# PWDTimer_8Lane.net
KiCad netlist of a schematic drawn in EAGLE
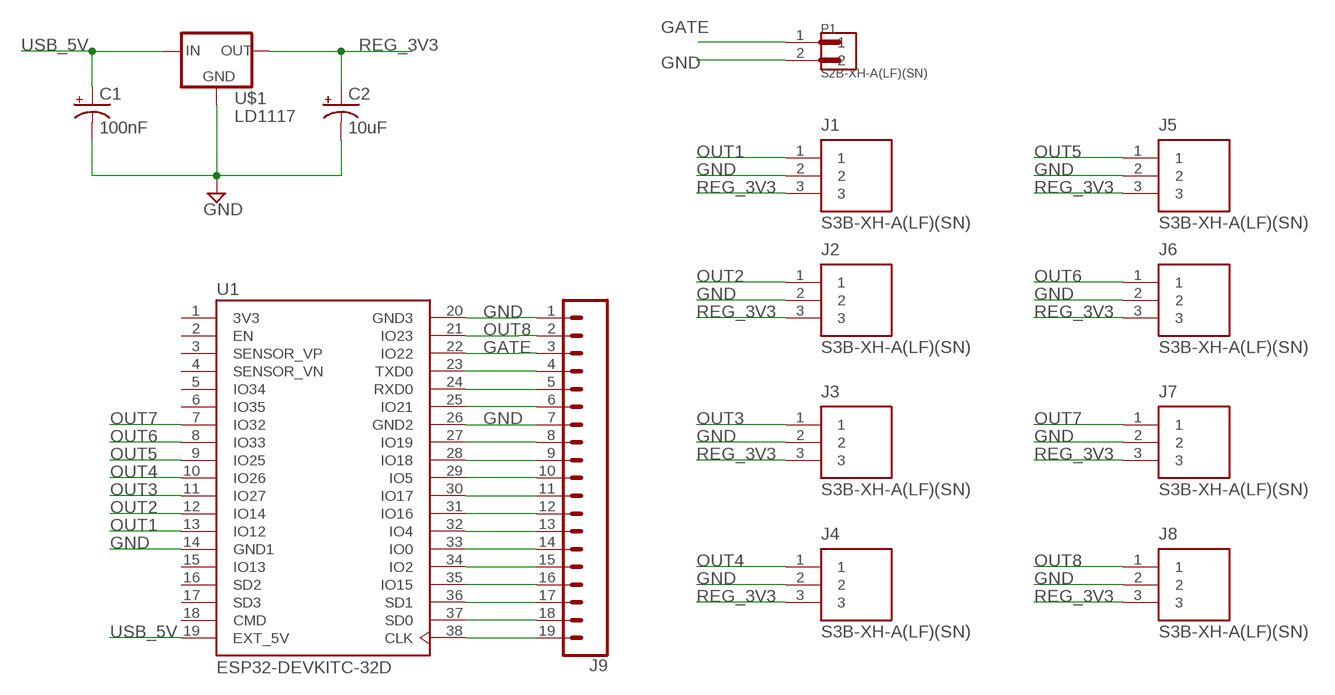
[diagram p0: schematic, sheet 1]

(export (version "E")
  (design (tool "Eeschema 10.0.6"))
  (components
    (comp (ref "C1")
      (value "100nF")
      (footprint "eagle-import:CPOL-RADIAL-2.5MM-5MM")
      (libsource (lib "eagle-import") (part "10UF-POLAR-RADIAL-2.5MM-25V-20%"))
    )
    (comp (ref "C2")
      (value "10uF")
      (footprint "eagle-import:CPOL-RADIAL-2.5MM-5MM")
      (libsource (lib "eagle-import") (part "10UF-POLAR-RADIAL-2.5MM-25V-20%"))
    )
    (comp (ref "J1")
      (value "S3B-XH-A(LF)(SN)")
      (footprint "eagle-import:JST_S3B-XH-A(LF)(SN)")
      (fields (field (name "MF") "JST Sales America Inc."))
      (libsource (lib "eagle-import") (part "S3B-XH-A(LF)(SN)"))
    )
    (comp (ref "J2")
      (value "S3B-XH-A(LF)(SN)")
      (footprint "eagle-import:JST_S3B-XH-A(LF)(SN)")
      (fields (field (name "MF") "JST Sales America Inc."))
      (libsource (lib "eagle-import") (part "S3B-XH-A(LF)(SN)"))
    )
    (comp (ref "J3")
      (value "S3B-XH-A(LF)(SN)")
      (footprint "eagle-import:JST_S3B-XH-A(LF)(SN)")
      (fields (field (name "MF") "JST Sales America Inc."))
      (libsource (lib "eagle-import") (part "S3B-XH-A(LF)(SN)"))
    )
    (comp (ref "J4")
      (value "S3B-XH-A(LF)(SN)")
      (footprint "eagle-import:JST_S3B-XH-A(LF)(SN)")
      (fields (field (name "MF") "JST Sales America Inc."))
      (libsource (lib "eagle-import") (part "S3B-XH-A(LF)(SN)"))
    )
    (comp (ref "J5")
      (value "S3B-XH-A(LF)(SN)")
      (footprint "eagle-import:JST_S3B-XH-A(LF)(SN)")
      (fields (field (name "MF") "JST Sales America Inc."))
      (libsource (lib "eagle-import") (part "S3B-XH-A(LF)(SN)"))
    )
    (comp (ref "J6")
      (value "S3B-XH-A(LF)(SN)")
      (footprint "eagle-import:JST_S3B-XH-A(LF)(SN)")
      (fields (field (name "MF") "JST Sales America Inc."))
      (libsource (lib "eagle-import") (part "S3B-XH-A(LF)(SN)"))
    )
    (comp (ref "J7")
      (value "S3B-XH-A(LF)(SN)")
      (footprint "eagle-import:JST_S3B-XH-A(LF)(SN)")
      (fields (field (name "MF") "JST Sales America Inc."))
      (libsource (lib "eagle-import") (part "S3B-XH-A(LF)(SN)"))
    )
    (comp (ref "J8")
      (value "S3B-XH-A(LF)(SN)")
      (footprint "eagle-import:JST_S3B-XH-A(LF)(SN)")
      (fields (field (name "MF") "JST Sales America Inc."))
      (libsource (lib "eagle-import") (part "S3B-XH-A(LF)(SN)"))
    )
    (comp (ref "J9")
      (value "CONN_191X19_NO_SILK")
      (footprint "eagle-import:1X19_NO_SILK")
      (libsource (lib "eagle-import") (part "CONN_191X19_NO_SILK"))
    )
    (comp (ref "P1")
      (value "S2B-XH-A(LF)(SN)")
      (footprint "eagle-import:JST_S2B-XH-A(LF)(SN)")
      (fields (field (name "MF") "JST Sales"))
      (libsource (lib "eagle-import") (part "S2B-XH-A(LF)(SN)"))
    )
    (comp (ref "U$1")
      (value "LD1117")
      (footprint "eagle-import:TO220")
      (fields (field (name "MF") "STMicroelectronics"))
      (libsource (lib "eagle-import") (part "LD1117"))
    )
    (comp (ref "U1")
      (value "ESP32-DEVKITC-32D")
      (footprint "eagle-import:MODULE_ESP32-DEVKITC-32D")
      (fields (field (name "MF") "Espressif Systems"))
      (libsource (lib "eagle-import") (part "ESP32-DEVKITC-32D"))
    )
  )
  (nets
    (net (code "1") (name "/3V3") (class "Default")
      (node (ref "U1") (pin "1") (pinfunction "3V3_1") (pintype "power_in"))
    )
    (net (code "2") (name "/GATE") (class "Default")
      (node (ref "J9") (pin "3") (pinfunction "3_3") (pintype "passive"))
      (node (ref "P1") (pin "1") (pinfunction "1_1") (pintype "passive"))
      (node (ref "U1") (pin "22") (pinfunction "IO22_22") (pintype "bidirectional"))
    )
    (net (code "3") (name "/OUT1") (class "Default")
      (node (ref "J1") (pin "1") (pinfunction "1_1") (pintype "passive"))
      (node (ref "U1") (pin "13") (pinfunction "IO12_13") (pintype "bidirectional"))
    )
    (net (code "4") (name "/OUT2") (class "Default")
      (node (ref "J2") (pin "1") (pinfunction "1_1") (pintype "passive"))
      (node (ref "U1") (pin "12") (pinfunction "IO14_12") (pintype "bidirectional"))
    )
    (net (code "5") (name "/OUT3") (class "Default")
      (node (ref "J3") (pin "1") (pinfunction "1_1") (pintype "passive"))
      (node (ref "U1") (pin "11") (pinfunction "IO27_11") (pintype "bidirectional"))
    )
    (net (code "6") (name "/OUT4") (class "Default")
      (node (ref "J4") (pin "1") (pinfunction "1_1") (pintype "passive"))
      (node (ref "U1") (pin "10") (pinfunction "IO26_10") (pintype "bidirectional"))
    )
    (net (code "7") (name "/OUT5") (class "Default")
      (node (ref "J5") (pin "1") (pinfunction "1_1") (pintype "passive"))
      (node (ref "U1") (pin "9") (pinfunction "IO25_9") (pintype "bidirectional"))
    )
    (net (code "8") (name "/OUT6") (class "Default")
      (node (ref "J6") (pin "1") (pinfunction "1_1") (pintype "passive"))
      (node (ref "U1") (pin "8") (pinfunction "IO33_8") (pintype "bidirectional"))
    )
    (net (code "9") (name "/OUT7") (class "Default")
      (node (ref "J7") (pin "1") (pinfunction "1_1") (pintype "passive"))
      (node (ref "U1") (pin "7") (pinfunction "IO32_7") (pintype "bidirectional"))
    )
    (net (code "10") (name "/OUT8") (class "Default")
      (node (ref "J8") (pin "1") (pinfunction "1_1") (pintype "passive"))
      (node (ref "J9") (pin "2") (pinfunction "2_2") (pintype "passive"))
      (node (ref "U1") (pin "21") (pinfunction "IO23_21") (pintype "bidirectional"))
    )
    (net (code "11") (name "/REG_3V3") (class "Default")
      (node (ref "C2") (pin "1") (pinfunction "+_1") (pintype "passive"))
      (node (ref "J1") (pin "3") (pinfunction "3_3") (pintype "passive"))
      (node (ref "J2") (pin "3") (pinfunction "3_3") (pintype "passive"))
      (node (ref "J3") (pin "3") (pinfunction "3_3") (pintype "passive"))
      (node (ref "J4") (pin "3") (pinfunction "3_3") (pintype "passive"))
      (node (ref "J5") (pin "3") (pinfunction "3_3") (pintype "passive"))
      (node (ref "J6") (pin "3") (pinfunction "3_3") (pintype "passive"))
      (node (ref "J7") (pin "3") (pinfunction "3_3") (pintype "passive"))
      (node (ref "J8") (pin "3") (pinfunction "3_3") (pintype "passive"))
      (node (ref "U$1") (pin "2") (pinfunction "OUT_2") (pintype "output"))
    )
    (net (code "12") (name "/USB_5V") (class "Default")
      (node (ref "C1") (pin "1") (pinfunction "+_1") (pintype "passive"))
      (node (ref "U$1") (pin "3") (pinfunction "IN_3") (pintype "input"))
      (node (ref "U1") (pin "19") (pinfunction "EXT_5V_19") (pintype "power_in"))
    )
    (net (code "13") (name "GND") (class "Default")
      (node (ref "C1") (pin "2") (pinfunction "-_2") (pintype "passive"))
      (node (ref "C2") (pin "2") (pinfunction "-_2") (pintype "passive"))
      (node (ref "J1") (pin "2") (pinfunction "2_2") (pintype "passive"))
      (node (ref "J2") (pin "2") (pinfunction "2_2") (pintype "passive"))
      (node (ref "J3") (pin "2") (pinfunction "2_2") (pintype "passive"))
      (node (ref "J4") (pin "2") (pinfunction "2_2") (pintype "passive"))
      (node (ref "J5") (pin "2") (pinfunction "2_2") (pintype "passive"))
      (node (ref "J6") (pin "2") (pinfunction "2_2") (pintype "passive"))
      (node (ref "J7") (pin "2") (pinfunction "2_2") (pintype "passive"))
      (node (ref "J8") (pin "2") (pinfunction "2_2") (pintype "passive"))
      (node (ref "J9") (pin "1") (pinfunction "1_1") (pintype "passive"))
      (node (ref "J9") (pin "7") (pinfunction "7_7") (pintype "passive"))
      (node (ref "P1") (pin "2") (pinfunction "2_2") (pintype "passive"))
      (node (ref "U$1") (pin "1") (pinfunction "GND_1") (pintype "input"))
      (node (ref "U1") (pin "14") (pinfunction "GND1_14") (pintype "power_in"))
      (node (ref "U1") (pin "20") (pinfunction "GND3_20") (pintype "power_in"))
      (node (ref "U1") (pin "26") (pinfunction "GND2_26") (pintype "power_in"))
    )
    (net (code "14") (name "Net-(U1-CLK)") (class "Default")
      (node (ref "J9") (pin "19") (pinfunction "19_19") (pintype "passive"))
      (node (ref "U1") (pin "38") (pinfunction "CLK_38") (pintype "input"))
    )
    (net (code "15") (name "Net-(U1-IO0)") (class "Default")
      (node (ref "J9") (pin "14") (pinfunction "14_14") (pintype "passive"))
      (node (ref "U1") (pin "33") (pinfunction "IO0_33") (pintype "bidirectional"))
    )
    (net (code "16") (name "Net-(U1-IO2)") (class "Default")
      (node (ref "J9") (pin "15") (pinfunction "15_15") (pintype "passive"))
      (node (ref "U1") (pin "34") (pinfunction "IO2_34") (pintype "bidirectional"))
    )
    (net (code "17") (name "Net-(U1-IO4)") (class "Default")
      (node (ref "J9") (pin "13") (pinfunction "13_13") (pintype "passive"))
      (node (ref "U1") (pin "32") (pinfunction "IO4_32") (pintype "bidirectional"))
    )
    (net (code "18") (name "Net-(U1-IO5)") (class "Default")
      (node (ref "J9") (pin "10") (pinfunction "10_10") (pintype "passive"))
      (node (ref "U1") (pin "29") (pinfunction "IO5_29") (pintype "bidirectional"))
    )
    (net (code "19") (name "Net-(U1-IO15)") (class "Default")
      (node (ref "J9") (pin "16") (pinfunction "16_16") (pintype "passive"))
      (node (ref "U1") (pin "35") (pinfunction "IO15_35") (pintype "bidirectional"))
    )
    (net (code "20") (name "Net-(U1-IO16)") (class "Default")
      (node (ref "J9") (pin "12") (pinfunction "12_12") (pintype "passive"))
      (node (ref "U1") (pin "31") (pinfunction "IO16_31") (pintype "bidirectional"))
    )
    (net (code "21") (name "Net-(U1-IO17)") (class "Default")
      (node (ref "J9") (pin "11") (pinfunction "11_11") (pintype "passive"))
      (node (ref "U1") (pin "30") (pinfunction "IO17_30") (pintype "bidirectional"))
    )
    (net (code "22") (name "Net-(U1-IO18)") (class "Default")
      (node (ref "J9") (pin "9") (pinfunction "9_9") (pintype "passive"))
      (node (ref "U1") (pin "28") (pinfunction "IO18_28") (pintype "bidirectional"))
    )
    (net (code "23") (name "Net-(U1-IO19)") (class "Default")
      (node (ref "J9") (pin "8") (pinfunction "8_8") (pintype "passive"))
      (node (ref "U1") (pin "27") (pinfunction "IO19_27") (pintype "bidirectional"))
    )
    (net (code "24") (name "Net-(U1-IO21)") (class "Default")
      (node (ref "J9") (pin "6") (pinfunction "6_6") (pintype "passive"))
      (node (ref "U1") (pin "25") (pinfunction "IO21_25") (pintype "bidirectional"))
    )
    (net (code "25") (name "Net-(U1-RXD0)") (class "Default")
      (node (ref "J9") (pin "5") (pinfunction "5_5") (pintype "passive"))
      (node (ref "U1") (pin "24") (pinfunction "RXD0_24") (pintype "input"))
    )
    (net (code "26") (name "Net-(U1-SD0)") (class "Default")
      (node (ref "J9") (pin "18") (pinfunction "18_18") (pintype "passive"))
      (node (ref "U1") (pin "37") (pinfunction "SD0_37") (pintype "bidirectional"))
    )
    (net (code "27") (name "Net-(U1-SD1)") (class "Default")
      (node (ref "J9") (pin "17") (pinfunction "17_17") (pintype "passive"))
      (node (ref "U1") (pin "36") (pinfunction "SD1_36") (pintype "bidirectional"))
    )
    (net (code "28") (name "Net-(U1-TXD0)") (class "Default")
      (node (ref "J9") (pin "4") (pinfunction "4_4") (pintype "passive"))
      (node (ref "U1") (pin "23") (pinfunction "TXD0_23") (pintype "output"))
    )
    (net (code "29") (name "unconnected-(U1-CMD-Pad18)") (class "Default")
      (node (ref "U1") (pin "18") (pinfunction "CMD_18") (pintype "bidirectional"))
    )
    (net (code "30") (name "unconnected-(U1-EN-Pad2)") (class "Default")
      (node (ref "U1") (pin "2") (pinfunction "EN_2") (pintype "input"))
    )
    (net (code "31") (name "unconnected-(U1-IO13-Pad15)") (class "Default")
      (node (ref "U1") (pin "15") (pinfunction "IO13_15") (pintype "bidirectional"))
    )
    (net (code "32") (name "unconnected-(U1-IO34-Pad5)") (class "Default")
      (node (ref "U1") (pin "5") (pinfunction "IO34_5") (pintype "bidirectional"))
    )
    (net (code "33") (name "unconnected-(U1-IO35-Pad6)") (class "Default")
      (node (ref "U1") (pin "6") (pinfunction "IO35_6") (pintype "bidirectional"))
    )
    (net (code "34") (name "unconnected-(U1-SD2-Pad16)") (class "Default")
      (node (ref "U1") (pin "16") (pinfunction "SD2_16") (pintype "bidirectional"))
    )
    (net (code "35") (name "unconnected-(U1-SD3-Pad17)") (class "Default")
      (node (ref "U1") (pin "17") (pinfunction "SD3_17") (pintype "bidirectional"))
    )
    (net (code "36") (name "unconnected-(U1-SENSOR_VN-Pad4)") (class "Default")
      (node (ref "U1") (pin "4") (pinfunction "SENSOR_VN_4") (pintype "input"))
    )
    (net (code "37") (name "unconnected-(U1-SENSOR_VP-Pad3)") (class "Default")
      (node (ref "U1") (pin "3") (pinfunction "SENSOR_VP_3") (pintype "input"))
    )
  )
)
